# MeasurevoltageCurrent1.net
KiCad netlist of a schematic drawn in Altium Designer
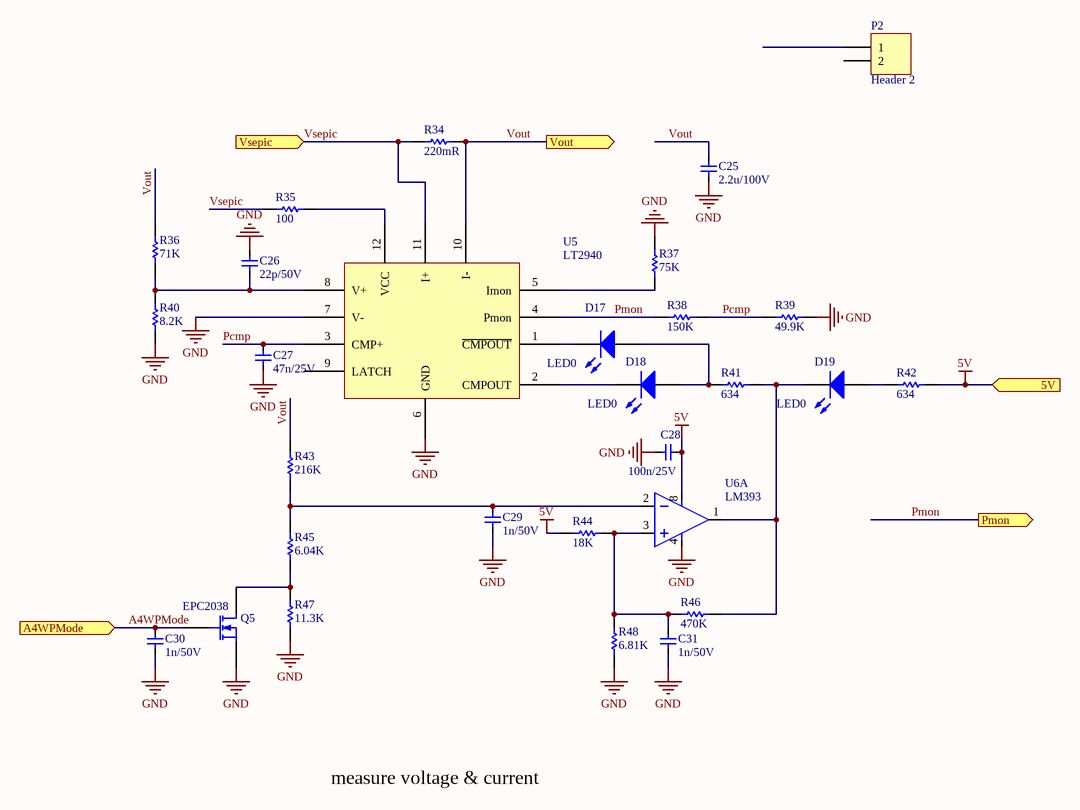
[diagram p0: MeasurevoltageCurrent1 .SchDoc]

(export (version "E")
  (design (tool "Eeschema 10.0.6"))
  (components
    (comp (ref "C25")
      (value "2.2u/100V")
      (footprint "0603")
      (description "Capacitor")
      (libsource (lib "5V1A1.0") (part "CAP1"))
    )
    (comp (ref "C26")
      (value "22p/50V")
      (footprint "0603")
      (description "Capacitor")
      (libsource (lib "5V1A1.0") (part "CAP1"))
    )
    (comp (ref "C27")
      (value "47n/25V")
      (footprint "0603")
      (description "Capacitor")
      (libsource (lib "5V1A1.0") (part "CAP1"))
    )
    (comp (ref "C28")
      (value "100n/25V")
      (footprint "0603")
      (description "Capacitor")
      (libsource (lib "5V1A1.0") (part "CAP1"))
    )
    (comp (ref "C29")
      (value "1n/50V")
      (footprint "0603")
      (description "Capacitor")
      (libsource (lib "5V1A1.0") (part "CAP1"))
    )
    (comp (ref "C30")
      (value "1n/50V")
      (footprint "0603")
      (description "Capacitor")
      (libsource (lib "5V1A1.0") (part "CAP1"))
    )
    (comp (ref "C31")
      (value "1n/50V")
      (footprint "0603")
      (description "Capacitor")
      (libsource (lib "5V1A1.0") (part "CAP1"))
    )
    (comp (ref "D17")
      (value "LED0")
      (footprint "LED0805")
      (description "Typical INFRARED GaAs LED")
      (fields (field (name "PUBLISHER") "Altium Limited"))
      (libsource (lib "Miscellaneous Devices") (part "LED0"))
    )
    (comp (ref "D18")
      (value "LED0")
      (footprint "LED0805")
      (description "Typical INFRARED GaAs LED")
      (fields (field (name "PUBLISHER") "Altium Limited"))
      (libsource (lib "Miscellaneous Devices") (part "LED0"))
    )
    (comp (ref "D19")
      (value "LED0")
      (footprint "LED0805")
      (description "Typical INFRARED GaAs LED")
      (fields (field (name "PUBLISHER") "Altium Limited"))
      (libsource (lib "Miscellaneous Devices") (part "LED0"))
    )
    (comp (ref "P2")
      (value "Header 2")
      (footprint "HDR1X2")
      (description "Header, 2-Pin")
      (fields (field (name "PUBLISHER") "Altium Limited"))
      (libsource (lib "Miscellaneous Connectors") (part "Header 2"))
    )
    (comp (ref "Q5")
      (value "EPC2038")
      (footprint "BGA100P9X9-81A")
      (description "N-Channel MOSFET")
      (fields (field (name "PUBLISHER") "Altium Limited"))
      (libsource (lib "Miscellaneous Devices") (part "MOSFET-N"))
    )
    (comp (ref "R34")
      (value "220mR")
      (footprint "0603")
      (description "Resistor")
      (fields (field (name "Comment") "Res1") (field (name "PUBLISHER") "Altium Limited"))
      (libsource (lib "Miscellaneous Devices") (part "Res1"))
    )
    (comp (ref "R35")
      (value "100")
      (footprint "0603")
      (description "Resistor")
      (fields (field (name "Comment") "Res1") (field (name "PUBLISHER") "Altium Limited"))
      (libsource (lib "Miscellaneous Devices") (part "Res1"))
    )
    (comp (ref "R36")
      (value "71K")
      (footprint "0603")
      (description "Resistor")
      (fields (field (name "Comment") "Res1") (field (name "PUBLISHER") "Altium Limited"))
      (libsource (lib "Miscellaneous Devices") (part "Res1"))
    )
    (comp (ref "R37")
      (value "75K")
      (footprint "0603")
      (description "Resistor")
      (fields (field (name "Comment") "Res1") (field (name "PUBLISHER") "Altium Limited"))
      (libsource (lib "Miscellaneous Devices") (part "Res1"))
    )
    (comp (ref "R38")
      (value "150K")
      (footprint "0603")
      (description "Resistor")
      (fields (field (name "Comment") "Res1") (field (name "PUBLISHER") "Altium Limited"))
      (libsource (lib "Miscellaneous Devices") (part "Res1"))
    )
    (comp (ref "R39")
      (value "49.9K")
      (footprint "0603")
      (description "Resistor")
      (fields (field (name "Comment") "Res1") (field (name "PUBLISHER") "Altium Limited"))
      (libsource (lib "Miscellaneous Devices") (part "Res1"))
    )
    (comp (ref "R40")
      (value "8.2K")
      (footprint "0603")
      (description "Resistor")
      (fields (field (name "Comment") "Res1") (field (name "PUBLISHER") "Altium Limited"))
      (libsource (lib "Miscellaneous Devices") (part "Res1"))
    )
    (comp (ref "R41")
      (value "634")
      (footprint "0603")
      (description "Resistor")
      (fields (field (name "Comment") "Res1") (field (name "PUBLISHER") "Altium Limited"))
      (libsource (lib "Miscellaneous Devices") (part "Res1"))
    )
    (comp (ref "R42")
      (value "634")
      (footprint "0603")
      (description "Resistor")
      (fields (field (name "Comment") "Res1") (field (name "PUBLISHER") "Altium Limited"))
      (libsource (lib "Miscellaneous Devices") (part "Res1"))
    )
    (comp (ref "R43")
      (value "216K")
      (footprint "0603")
      (description "Resistor")
      (fields (field (name "Comment") "Res1") (field (name "PUBLISHER") "Altium Limited"))
      (libsource (lib "Miscellaneous Devices") (part "Res1"))
    )
    (comp (ref "R44")
      (value "18K")
      (footprint "0603")
      (description "Resistor")
      (fields (field (name "Comment") "Res1") (field (name "PUBLISHER") "Altium Limited"))
      (libsource (lib "Miscellaneous Devices") (part "Res1"))
    )
    (comp (ref "R45")
      (value "6.04K")
      (footprint "0603")
      (description "Resistor")
      (fields (field (name "Comment") "Res1") (field (name "PUBLISHER") "Altium Limited"))
      (libsource (lib "Miscellaneous Devices") (part "Res1"))
    )
    (comp (ref "R46")
      (value "470K")
      (footprint "0603")
      (description "Resistor")
      (fields (field (name "Comment") "Res1") (field (name "PUBLISHER") "Altium Limited"))
      (libsource (lib "Miscellaneous Devices") (part "Res1"))
    )
    (comp (ref "R47")
      (value "11.3K")
      (footprint "0603")
      (description "Resistor")
      (fields (field (name "Comment") "Res1") (field (name "PUBLISHER") "Altium Limited"))
      (libsource (lib "Miscellaneous Devices") (part "Res1"))
    )
    (comp (ref "R48")
      (value "6.81K")
      (footprint "0603")
      (description "Resistor")
      (fields (field (name "Comment") "Res1") (field (name "PUBLISHER") "Altium Limited"))
      (libsource (lib "Miscellaneous Devices") (part "Res1"))
    )
    (comp (ref "U5")
      (value "LT2940")
      (footprint "TSOP65P500X100-12N")
      (libsource (lib "5V1A1.0") (part "LT2940"))
    )
    (comp (ref "U6")
      (value "LM393")
      (footprint "Miscellaneous Devices:SO8_L")
      (libsource (lib "5V1A1.1") (part "LM393"))
    )
  )
  (nets
    (net (code "1") (name "/A4WPMode") (class "Default")
      (node (ref "C30") (pin "1") (pinfunction "1_1") (pintype "passive"))
      (node (ref "Q5") (pin "2") (pinfunction "G_2") (pintype "passive"))
    )
    (net (code "2") (name "/Pcmp") (class "Default")
      (node (ref "C27") (pin "1") (pinfunction "1_1") (pintype "passive"))
      (node (ref "R38") (pin "2") (pinfunction "2_2") (pintype "passive"))
      (node (ref "R39") (pin "1") (pinfunction "1_1") (pintype "passive"))
      (node (ref "U5") (pin "3") (pinfunction "CMP+_3") (pintype "passive"))
    )
    (net (code "3") (name "/Pmon") (class "Default")
      (node (ref "R38") (pin "1") (pinfunction "1_1") (pintype "passive"))
      (node (ref "U5") (pin "4") (pinfunction "Pmon_4") (pintype "passive"))
    )
    (net (code "4") (name "/Vout") (class "Default")
      (node (ref "C25") (pin "2") (pinfunction "2_2") (pintype "passive"))
      (node (ref "R34") (pin "1") (pinfunction "1_1") (pintype "passive"))
      (node (ref "R36") (pin "2") (pinfunction "2_2") (pintype "passive"))
      (node (ref "R43") (pin "2") (pinfunction "2_2") (pintype "passive"))
      (node (ref "U5") (pin "10") (pinfunction "I-_10") (pintype "passive"))
    )
    (net (code "5") (name "/Vsepic") (class "Default")
      (node (ref "R34") (pin "2") (pinfunction "2_2") (pintype "passive"))
      (node (ref "R35") (pin "2") (pinfunction "2_2") (pintype "passive"))
      (node (ref "U5") (pin "11") (pinfunction "I+_11") (pintype "passive"))
    )
    (net (code "6") (name "5V") (class "Default")
      (node (ref "C28") (pin "1") (pinfunction "1_1") (pintype "passive"))
      (node (ref "R42") (pin "2") (pinfunction "2_2") (pintype "passive"))
      (node (ref "R44") (pin "1") (pinfunction "1_1") (pintype "passive"))
      (node (ref "U6") (pin "8") (pinfunction "gnd_8") (pintype "passive"))
    )
    (net (code "7") (name "GND") (class "Default")
      (node (ref "C25") (pin "1") (pinfunction "1_1") (pintype "passive"))
      (node (ref "C26") (pin "1") (pinfunction "1_1") (pintype "passive"))
      (node (ref "C27") (pin "2") (pinfunction "2_2") (pintype "passive"))
      (node (ref "C28") (pin "2") (pinfunction "2_2") (pintype "passive"))
      (node (ref "C29") (pin "2") (pinfunction "2_2") (pintype "passive"))
      (node (ref "C30") (pin "2") (pinfunction "2_2") (pintype "passive"))
      (node (ref "C31") (pin "2") (pinfunction "2_2") (pintype "passive"))
      (node (ref "Q5") (pin "3") (pinfunction "S_3") (pintype "passive"))
      (node (ref "R37") (pin "1") (pinfunction "1_1") (pintype "passive"))
      (node (ref "R39") (pin "2") (pinfunction "2_2") (pintype "passive"))
      (node (ref "R40") (pin "1") (pinfunction "1_1") (pintype "passive"))
      (node (ref "R47") (pin "1") (pinfunction "1_1") (pintype "passive"))
      (node (ref "R48") (pin "1") (pinfunction "1_1") (pintype "passive"))
      (node (ref "U5") (pin "6") (pinfunction "GND_6") (pintype "passive"))
      (node (ref "U5") (pin "7") (pinfunction "V-_7") (pintype "passive"))
      (node (ref "U6") (pin "4") (pinfunction "vcc_4") (pintype "passive"))
    )
    (net (code "8") (name "Net-(C29-Pad1)") (class "Default")
      (node (ref "C29") (pin "1") (pinfunction "1_1") (pintype "passive"))
      (node (ref "R43") (pin "1") (pinfunction "1_1") (pintype "passive"))
      (node (ref "R45") (pin "2") (pinfunction "2_2") (pintype "passive"))
      (node (ref "U6") (pin "2") (pinfunction "2_2") (pintype "passive"))
    )
    (net (code "9") (name "Net-(C31-Pad1)") (class "Default")
      (node (ref "C31") (pin "1") (pinfunction "1_1") (pintype "passive"))
      (node (ref "R44") (pin "2") (pinfunction "2_2") (pintype "passive"))
      (node (ref "R46") (pin "1") (pinfunction "1_1") (pintype "passive"))
      (node (ref "R48") (pin "2") (pinfunction "2_2") (pintype "passive"))
      (node (ref "U6") (pin "3") (pinfunction "3_3") (pintype "passive"))
    )
    (net (code "10") (name "Net-(D17-A)") (class "Default")
      (node (ref "D17") (pin "1") (pinfunction "A_1") (pintype "passive"))
      (node (ref "D18") (pin "1") (pinfunction "A_1") (pintype "passive"))
      (node (ref "R41") (pin "1") (pinfunction "1_1") (pintype "passive"))
    )
    (net (code "11") (name "Net-(D17-K)") (class "Default")
      (node (ref "D17") (pin "2") (pinfunction "K_2") (pintype "passive"))
      (node (ref "U5") (pin "1") (pinfunction "~{CMPOUT}_1") (pintype "passive"))
    )
    (net (code "12") (name "Net-(D18-K)") (class "Default")
      (node (ref "D18") (pin "2") (pinfunction "K_2") (pintype "passive"))
      (node (ref "U5") (pin "2") (pinfunction "CMPOUT_2") (pintype "passive"))
    )
    (net (code "13") (name "Net-(D19-A)") (class "Default")
      (node (ref "D19") (pin "1") (pinfunction "A_1") (pintype "passive"))
      (node (ref "R42") (pin "1") (pinfunction "1_1") (pintype "passive"))
    )
    (net (code "14") (name "Net-(D19-K)") (class "Default")
      (node (ref "D19") (pin "2") (pinfunction "K_2") (pintype "passive"))
      (node (ref "R41") (pin "2") (pinfunction "2_2") (pintype "passive"))
      (node (ref "R46") (pin "2") (pinfunction "2_2") (pintype "passive"))
      (node (ref "U6") (pin "1") (pinfunction "1_1") (pintype "passive"))
    )
    (net (code "15") (name "Net-(Q5-D)") (class "Default")
      (node (ref "Q5") (pin "1") (pinfunction "D_1") (pintype "passive"))
      (node (ref "R45") (pin "1") (pinfunction "1_1") (pintype "passive"))
      (node (ref "R47") (pin "2") (pinfunction "2_2") (pintype "passive"))
    )
    (net (code "16") (name "Net-(U5-Imon)") (class "Default")
      (node (ref "R37") (pin "2") (pinfunction "2_2") (pintype "passive"))
      (node (ref "U5") (pin "5") (pinfunction "Imon_5") (pintype "passive"))
    )
    (net (code "17") (name "Net-(U5-V+)") (class "Default")
      (node (ref "C26") (pin "2") (pinfunction "2_2") (pintype "passive"))
      (node (ref "R36") (pin "1") (pinfunction "1_1") (pintype "passive"))
      (node (ref "R40") (pin "2") (pinfunction "2_2") (pintype "passive"))
      (node (ref "U5") (pin "8") (pinfunction "V+_8") (pintype "passive"))
    )
    (net (code "18") (name "Net-(U5-VCC)") (class "Default")
      (node (ref "R35") (pin "1") (pinfunction "1_1") (pintype "passive"))
      (node (ref "U5") (pin "12") (pinfunction "VCC_12") (pintype "passive"))
    )
    (net (code "19") (name "unconnected-(P2-Pad1)") (class "Default")
      (node (ref "P2") (pin "1") (pinfunction "1_1") (pintype "passive"))
    )
    (net (code "20") (name "unconnected-(P2-Pad2)") (class "Default")
      (node (ref "P2") (pin "2") (pinfunction "2_2") (pintype "passive"))
    )
    (net (code "21") (name "unconnected-(U5-LATCH-Pad9)") (class "Default")
      (node (ref "U5") (pin "9") (pinfunction "LATCH_9") (pintype "passive"))
    )
  )
)
